# v0.net
KiCad netlist of a schematic drawn in EAGLE
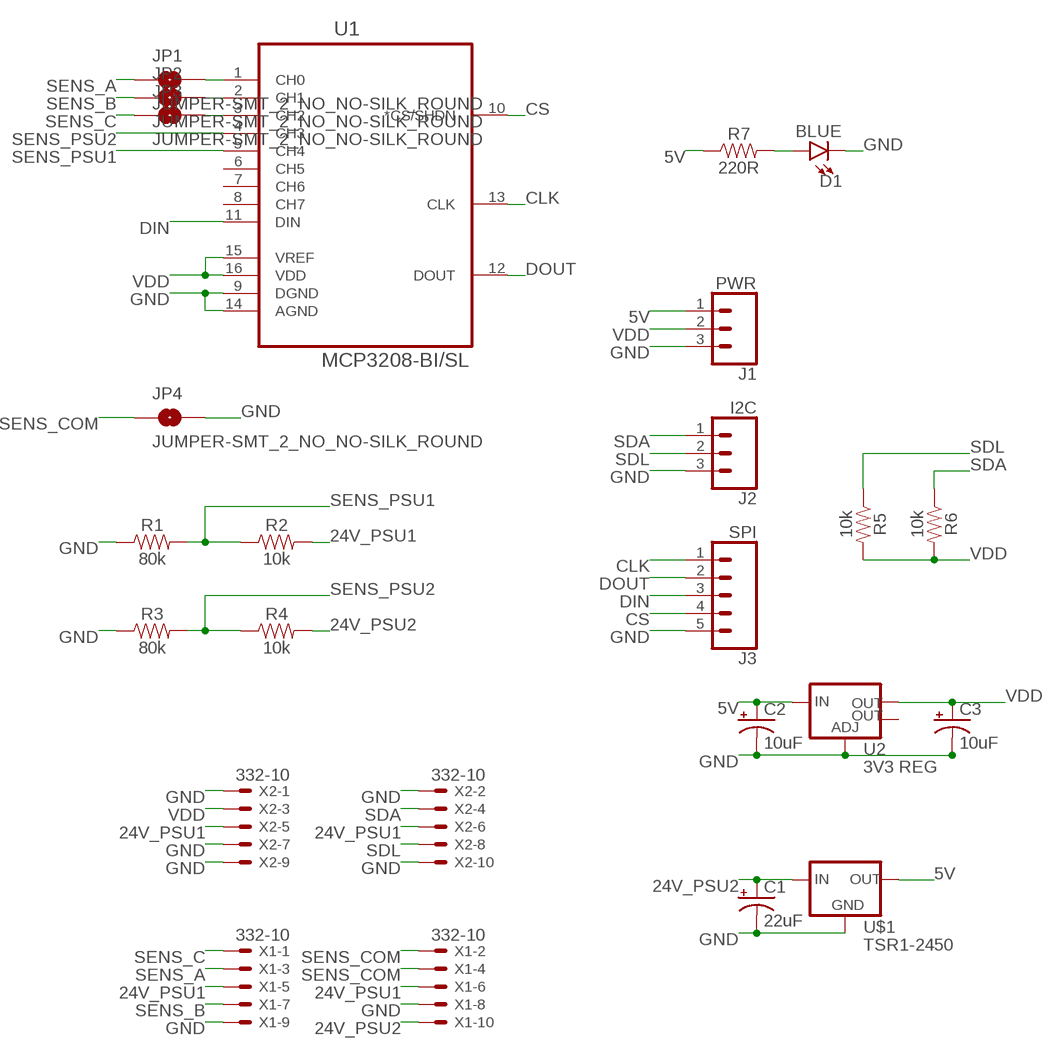
[diagram p0: schematic, sheet 1]

(export (version "E")
  (design (tool "Eeschema 10.0.6"))
  (components
    (comp (ref "C1")
      (value "22uF")
      (footprint "eagle-import:EIA3216")
      (libsource (lib "eagle-import") (part "10UF-POLAR-EIA3216-16V-10%(TANT)"))
    )
    (comp (ref "C2")
      (value "10uF")
      (footprint "eagle-import:EIA3216")
      (libsource (lib "eagle-import") (part "10UF-POLAR-EIA3216-16V-10%(TANT)"))
    )
    (comp (ref "C3")
      (value "10uF")
      (footprint "eagle-import:EIA3216")
      (libsource (lib "eagle-import") (part "10UF-POLAR-EIA3216-16V-10%(TANT)"))
    )
    (comp (ref "D1")
      (value "BLUE")
      (footprint "eagle-import:LED-0603")
      (libsource (lib "eagle-import") (part "LED-BLUE0603"))
    )
    (comp (ref "J1")
      (value "PWR")
      (footprint "eagle-import:1X03")
      (libsource (lib "eagle-import") (part "CONN_03"))
    )
    (comp (ref "J2")
      (value "I2C")
      (footprint "eagle-import:1X03")
      (libsource (lib "eagle-import") (part "CONN_03"))
    )
    (comp (ref "J3")
      (value "SPI")
      (footprint "eagle-import:1X05")
      (libsource (lib "eagle-import") (part "CONN_05"))
    )
    (comp (ref "JP1")
      (value "JUMPER-SMT_2_NO_NO-SILK_ROUND")
      (footprint "eagle-import:SMT-JUMPER_2_NO_NO-SILK_ROUND")
      (libsource (lib "eagle-import") (part "JUMPER-SMT_2_NO_NO-SILK_ROUND"))
    )
    (comp (ref "JP2")
      (value "JUMPER-SMT_2_NO_NO-SILK_ROUND")
      (footprint "eagle-import:SMT-JUMPER_2_NO_NO-SILK_ROUND")
      (libsource (lib "eagle-import") (part "JUMPER-SMT_2_NO_NO-SILK_ROUND"))
    )
    (comp (ref "JP3")
      (value "JUMPER-SMT_2_NO_NO-SILK_ROUND")
      (footprint "eagle-import:SMT-JUMPER_2_NO_NO-SILK_ROUND")
      (libsource (lib "eagle-import") (part "JUMPER-SMT_2_NO_NO-SILK_ROUND"))
    )
    (comp (ref "JP4")
      (value "JUMPER-SMT_2_NO_NO-SILK_ROUND")
      (footprint "eagle-import:SMT-JUMPER_2_NO_NO-SILK_ROUND")
      (libsource (lib "eagle-import") (part "JUMPER-SMT_2_NO_NO-SILK_ROUND"))
    )
    (comp (ref "R1")
      (value "80k")
      (footprint "eagle-import:0805")
      (libsource (lib "eagle-import") (part "RESISTOR0805"))
    )
    (comp (ref "R2")
      (value "10k")
      (footprint "eagle-import:0805")
      (libsource (lib "eagle-import") (part "RESISTOR0805"))
    )
    (comp (ref "R3")
      (value "80k")
      (footprint "eagle-import:0805")
      (libsource (lib "eagle-import") (part "RESISTOR0805"))
    )
    (comp (ref "R4")
      (value "10k")
      (footprint "eagle-import:0805")
      (libsource (lib "eagle-import") (part "RESISTOR0805"))
    )
    (comp (ref "R5")
      (value "10k")
      (footprint "eagle-import:0805")
      (libsource (lib "eagle-import") (part "RESISTOR0805"))
    )
    (comp (ref "R6")
      (value "10k")
      (footprint "eagle-import:0805")
      (libsource (lib "eagle-import") (part "RESISTOR0805"))
    )
    (comp (ref "R7")
      (value "220R")
      (footprint "eagle-import:0805")
      (libsource (lib "eagle-import") (part "RESISTOR0805"))
    )
    (comp (ref "U$1")
      (value "TSR1-2450")
      (footprint "eagle-import:TSR1-2450")
      (fields (field (name "MF") "Tracopower") (field (name "MP") "TSR 1-2450"))
      (libsource (lib "eagle-import") (part "TSR1-2450"))
    )
    (comp (ref "U1")
      (value "MCP3208-BI/SL")
      (footprint "eagle-import:SOIC127P600X175-16N")
      (fields (field (name "MF") "Microchip"))
      (libsource (lib "eagle-import") (part "MCP3208-BI/SL"))
    )
    (comp (ref "U2")
      (value "3V3 REG")
      (footprint "eagle-import:SOT223")
      (libsource (lib "eagle-import") (part "V_REG_LM1117SOT223"))
    )
    (comp (ref "X1")
      (value "332-10")
      (footprint "eagle-import:332-10")
      (libsource (lib "eagle-import") (part "332-10"))
    )
    (comp (ref "X2")
      (value "332-10")
      (footprint "eagle-import:332-10")
      (libsource (lib "eagle-import") (part "332-10"))
    )
  )
  (nets
    (net (code "1") (name "/5V") (class "Default")
      (node (ref "C2") (pin "+") (pinfunction "+_+") (pintype "passive"))
      (node (ref "J1") (pin "1") (pinfunction "1_1") (pintype "passive"))
      (node (ref "R7") (pin "1") (pinfunction "1_1") (pintype "passive"))
      (node (ref "U$1") (pin "3") (pinfunction "OUT_3") (pintype "passive"))
      (node (ref "U2") (pin "3") (pinfunction "IN_3") (pintype "input"))
    )
    (net (code "2") (name "/24V_PSU1") (class "Default")
      (node (ref "R2") (pin "2") (pinfunction "2_2") (pintype "passive"))
      (node (ref "X1") (pin "5") (pinfunction "S_5") (pintype "passive"))
      (node (ref "X1") (pin "6") (pinfunction "S_6") (pintype "passive"))
      (node (ref "X2") (pin "5") (pinfunction "S_5") (pintype "passive"))
      (node (ref "X2") (pin "6") (pinfunction "S_6") (pintype "passive"))
    )
    (net (code "3") (name "/24V_PSU2") (class "Default")
      (node (ref "C1") (pin "+") (pinfunction "+_+") (pintype "passive"))
      (node (ref "R4") (pin "2") (pinfunction "2_2") (pintype "passive"))
      (node (ref "U$1") (pin "1") (pinfunction "IN_1") (pintype "input"))
      (node (ref "X1") (pin "10") (pinfunction "S_10") (pintype "passive"))
    )
    (net (code "4") (name "/CLK") (class "Default")
      (node (ref "J3") (pin "1") (pinfunction "1_1") (pintype "passive"))
      (node (ref "U1") (pin "13") (pinfunction "CLK_13") (pintype "input"))
    )
    (net (code "5") (name "/CS") (class "Default")
      (node (ref "J3") (pin "4") (pinfunction "4_4") (pintype "passive"))
      (node (ref "U1") (pin "10") (pinfunction "*CS/SHDN_10") (pintype "input"))
    )
    (net (code "6") (name "/DIN") (class "Default")
      (node (ref "J3") (pin "3") (pinfunction "3_3") (pintype "passive"))
      (node (ref "U1") (pin "11") (pinfunction "DIN_11") (pintype "input"))
    )
    (net (code "7") (name "/DOUT") (class "Default")
      (node (ref "J3") (pin "2") (pinfunction "2_2") (pintype "passive"))
      (node (ref "U1") (pin "12") (pinfunction "DOUT_12") (pintype "output"))
    )
    (net (code "8") (name "/GND") (class "Default")
      (node (ref "C1") (pin "-") (pinfunction "-_-") (pintype "passive"))
      (node (ref "C2") (pin "-") (pinfunction "-_-") (pintype "passive"))
      (node (ref "C3") (pin "-") (pinfunction "-_-") (pintype "passive"))
      (node (ref "D1") (pin "C") (pinfunction "C_C") (pintype "passive"))
      (node (ref "J1") (pin "3") (pinfunction "3_3") (pintype "passive"))
      (node (ref "J2") (pin "3") (pinfunction "3_3") (pintype "passive"))
      (node (ref "J3") (pin "5") (pinfunction "5_5") (pintype "passive"))
      (node (ref "JP4") (pin "2") (pinfunction "2_2") (pintype "passive"))
      (node (ref "R1") (pin "1") (pinfunction "1_1") (pintype "passive"))
      (node (ref "R3") (pin "1") (pinfunction "1_1") (pintype "passive"))
      (node (ref "U$1") (pin "2") (pinfunction "GND_2") (pintype "input"))
      (node (ref "U1") (pin "14") (pinfunction "AGND_14") (pintype "passive"))
      (node (ref "U1") (pin "9") (pinfunction "DGND_9") (pintype "passive"))
      (node (ref "U2") (pin "1") (pinfunction "ADJ_1") (pintype "input"))
      (node (ref "X1") (pin "8") (pinfunction "S_8") (pintype "passive"))
      (node (ref "X1") (pin "9") (pinfunction "S_9") (pintype "passive"))
      (node (ref "X2") (pin "1") (pinfunction "S_1") (pintype "passive"))
      (node (ref "X2") (pin "10") (pinfunction "S_10") (pintype "passive"))
      (node (ref "X2") (pin "2") (pinfunction "S_2") (pintype "passive"))
      (node (ref "X2") (pin "7") (pinfunction "S_7") (pintype "passive"))
      (node (ref "X2") (pin "9") (pinfunction "S_9") (pintype "passive"))
    )
    (net (code "9") (name "/SDA") (class "Default")
      (node (ref "J2") (pin "1") (pinfunction "1_1") (pintype "passive"))
      (node (ref "R6") (pin "1") (pinfunction "1_1") (pintype "passive"))
      (node (ref "X2") (pin "4") (pinfunction "S_4") (pintype "passive"))
    )
    (net (code "10") (name "/SDL") (class "Default")
      (node (ref "J2") (pin "2") (pinfunction "2_2") (pintype "passive"))
      (node (ref "R5") (pin "1") (pinfunction "1_1") (pintype "passive"))
      (node (ref "X2") (pin "8") (pinfunction "S_8") (pintype "passive"))
    )
    (net (code "11") (name "/SENS_A") (class "Default")
      (node (ref "JP1") (pin "1") (pinfunction "1_1") (pintype "passive"))
      (node (ref "X1") (pin "3") (pinfunction "S_3") (pintype "passive"))
    )
    (net (code "12") (name "/SENS_B") (class "Default")
      (node (ref "JP2") (pin "1") (pinfunction "1_1") (pintype "passive"))
      (node (ref "X1") (pin "7") (pinfunction "S_7") (pintype "passive"))
    )
    (net (code "13") (name "/SENS_C") (class "Default")
      (node (ref "JP3") (pin "1") (pinfunction "1_1") (pintype "passive"))
      (node (ref "X1") (pin "1") (pinfunction "S_1") (pintype "passive"))
    )
    (net (code "14") (name "/SENS_COM") (class "Default")
      (node (ref "JP4") (pin "1") (pinfunction "1_1") (pintype "passive"))
      (node (ref "X1") (pin "2") (pinfunction "S_2") (pintype "passive"))
      (node (ref "X1") (pin "4") (pinfunction "S_4") (pintype "passive"))
    )
    (net (code "15") (name "/SENS_PSU1") (class "Default")
      (node (ref "R1") (pin "2") (pinfunction "2_2") (pintype "passive"))
      (node (ref "R2") (pin "1") (pinfunction "1_1") (pintype "passive"))
      (node (ref "U1") (pin "5") (pinfunction "CH4_5") (pintype "input"))
    )
    (net (code "16") (name "/SENS_PSU2") (class "Default")
      (node (ref "R3") (pin "2") (pinfunction "2_2") (pintype "passive"))
      (node (ref "R4") (pin "1") (pinfunction "1_1") (pintype "passive"))
      (node (ref "U1") (pin "4") (pinfunction "CH3_4") (pintype "input"))
    )
    (net (code "17") (name "/VDD") (class "Default")
      (node (ref "C3") (pin "+") (pinfunction "+_+") (pintype "passive"))
      (node (ref "J1") (pin "2") (pinfunction "2_2") (pintype "passive"))
      (node (ref "R5") (pin "2") (pinfunction "2_2") (pintype "passive"))
      (node (ref "R6") (pin "2") (pinfunction "2_2") (pintype "passive"))
      (node (ref "U1") (pin "15") (pinfunction "VREF_15") (pintype "input"))
      (node (ref "U1") (pin "16") (pinfunction "VDD_16") (pintype "power_in"))
      (node (ref "U2") (pin "2") (pinfunction "OUT_2") (pintype "output"))
      (node (ref "X2") (pin "3") (pinfunction "S_3") (pintype "passive"))
    )
    (net (code "18") (name "Net-(D1-PadA)") (class "Default")
      (node (ref "D1") (pin "A") (pinfunction "A_A") (pintype "passive"))
      (node (ref "R7") (pin "2") (pinfunction "2_2") (pintype "passive"))
    )
    (net (code "19") (name "Net-(U1-CH0)") (class "Default")
      (node (ref "JP1") (pin "2") (pinfunction "2_2") (pintype "passive"))
      (node (ref "U1") (pin "1") (pinfunction "CH0_1") (pintype "input"))
    )
    (net (code "20") (name "Net-(U1-CH1)") (class "Default")
      (node (ref "JP2") (pin "2") (pinfunction "2_2") (pintype "passive"))
      (node (ref "U1") (pin "2") (pinfunction "CH1_2") (pintype "input"))
    )
    (net (code "21") (name "Net-(U1-CH2)") (class "Default")
      (node (ref "JP3") (pin "2") (pinfunction "2_2") (pintype "passive"))
      (node (ref "U1") (pin "3") (pinfunction "CH2_3") (pintype "input"))
    )
    (net (code "22") (name "unconnected-(U1-CH5-Pad6)") (class "Default")
      (node (ref "U1") (pin "6") (pinfunction "CH5_6") (pintype "input"))
    )
    (net (code "23") (name "unconnected-(U1-CH6-Pad7)") (class "Default")
      (node (ref "U1") (pin "7") (pinfunction "CH6_7") (pintype "input"))
    )
    (net (code "24") (name "unconnected-(U1-CH7-Pad8)") (class "Default")
      (node (ref "U1") (pin "8") (pinfunction "CH7_8") (pintype "input"))
    )
    (net (code "25") (name "unconnected-(U2-OUT-Pad4)") (class "Default")
      (node (ref "U2") (pin "4") (pinfunction "OUT_4") (pintype "output"))
    )
  )
)
